# YBDuino.net
KiCad netlist of a schematic drawn in EAGLE
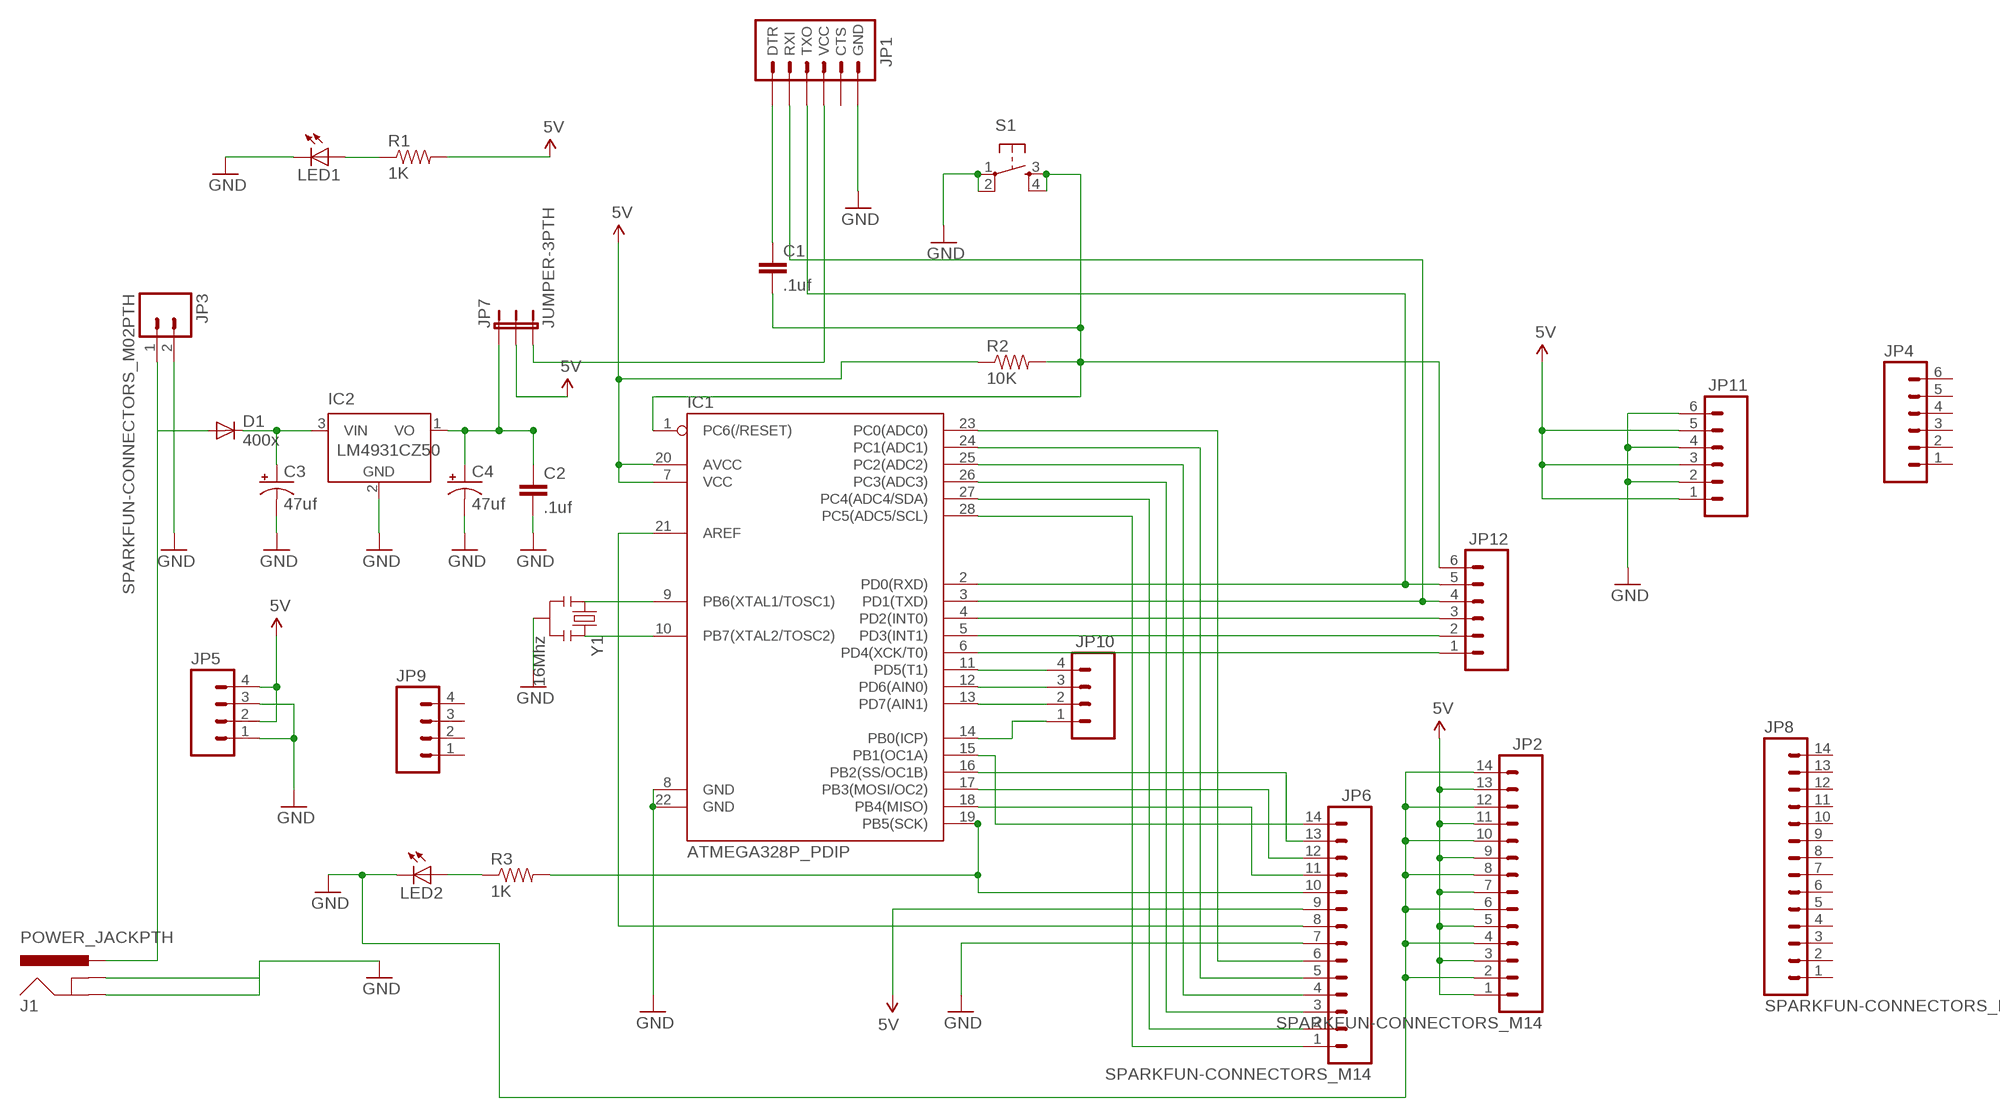
[diagram p0: schematic, sheet 1]

(export (version "E")
  (design (tool "Eeschema 10.0.6"))
  (components
    (comp (ref "C1")
      (value ".1uf")
      (footprint "eagle-import:CAP-PTH-SMALL")
      (libsource (lib "eagle-import") (part "CAPPTH"))
    )
    (comp (ref "C2")
      (value ".1uf")
      (footprint "eagle-import:CAP-PTH-SMALL")
      (libsource (lib "eagle-import") (part "CAPPTH"))
    )
    (comp (ref "C3")
      (value "47uf")
      (footprint "eagle-import:CPOL-RADIAL-100UF-25V")
      (libsource (lib "eagle-import") (part "CAP_POLPTH1"))
    )
    (comp (ref "C4")
      (value "47uf")
      (footprint "eagle-import:CPOL-RADIAL-100UF-25V")
      (libsource (lib "eagle-import") (part "CAP_POLPTH1"))
    )
    (comp (ref "D1")
      (value "400x")
      (footprint "eagle-import:C1702-05")
      (libsource (lib "eagle-import") (part "DIODE-C1702-05"))
    )
    (comp (ref "IC1")
      (value "ATMEGA328P_PDIP")
      (footprint "eagle-import:DIL28-3")
      (libsource (lib "eagle-import") (part "ATMEGA328P_PDIP"))
    )
    (comp (ref "IC2")
      (value "LM4931CZ50")
      (footprint "eagle-import:TO92")
      (fields (field (name "MF") "NATIONAL SEMICONDUCTOR") (field (name "MPN") "LM2936Z-3.0/NOPB"))
      (libsource (lib "eagle-import") (part "LM2936?Z-3.0"))
    )
    (comp (ref "J1")
      (value "POWER_JACKPTH")
      (footprint "eagle-import:POWER_JACK_PTH")
      (libsource (lib "eagle-import") (part "POWER_JACKPTH"))
    )
    (comp (ref "JP1")
      (value "SPARKFUN-CONNECTORS_ARDUINO_SERIAL_PROGRAMPTH-KIT")
      (footprint "eagle-import:SPARKFUN-CONNECTORS_1X06-KIT")
      (libsource (lib "eagle-import") (part "SPARKFUN-CONNECTORS_ARDUINO_SERIAL_PROGRAMPTH-KIT"))
    )
    (comp (ref "JP2")
      (value "SPARKFUN-CONNECTORS_M14")
      (footprint "eagle-import:SPARKFUN-CONNECTORS_1X14")
      (libsource (lib "eagle-import") (part "SPARKFUN-CONNECTORS_M14"))
    )
    (comp (ref "JP3")
      (value "SPARKFUN-CONNECTORS_M02PTH")
      (footprint "eagle-import:SPARKFUN-CONNECTORS_1X02")
      (libsource (lib "eagle-import") (part "SPARKFUN-CONNECTORS_M02PTH"))
    )
    (comp (ref "JP4")
      (value "SPARKFUN-CONNECTORS_M06SIP")
      (footprint "eagle-import:SPARKFUN-CONNECTORS_1X06")
      (libsource (lib "eagle-import") (part "SPARKFUN-CONNECTORS_M06SIP"))
    )
    (comp (ref "JP5")
      (value "SPARKFUN-CONNECTORS_M041X04_NO_SILK")
      (footprint "eagle-import:SPARKFUN-CONNECTORS_1X04_NO_SILK")
      (libsource (lib "eagle-import") (part "SPARKFUN-CONNECTORS_M041X04_NO_SILK"))
    )
    (comp (ref "JP6")
      (value "SPARKFUN-CONNECTORS_M14")
      (footprint "eagle-import:SPARKFUN-CONNECTORS_1X14")
      (libsource (lib "eagle-import") (part "SPARKFUN-CONNECTORS_M14"))
    )
    (comp (ref "JP7")
      (value "JUMPER-3PTH")
      (footprint "eagle-import:1X03")
      (libsource (lib "eagle-import") (part "JUMPER-3PTH"))
    )
    (comp (ref "JP8")
      (value "SPARKFUN-CONNECTORS_M14")
      (footprint "eagle-import:SPARKFUN-CONNECTORS_1X14")
      (libsource (lib "eagle-import") (part "SPARKFUN-CONNECTORS_M14"))
    )
    (comp (ref "JP9")
      (value "SPARKFUN-CONNECTORS_M041X04_NO_SILK")
      (footprint "eagle-import:SPARKFUN-CONNECTORS_1X04_NO_SILK")
      (libsource (lib "eagle-import") (part "SPARKFUN-CONNECTORS_M041X04_NO_SILK"))
    )
    (comp (ref "JP10")
      (value "SPARKFUN-CONNECTORS_M041X04_NO_SILK")
      (footprint "eagle-import:SPARKFUN-CONNECTORS_1X04_NO_SILK")
      (libsource (lib "eagle-import") (part "SPARKFUN-CONNECTORS_M041X04_NO_SILK"))
    )
    (comp (ref "JP11")
      (value "SPARKFUN-CONNECTORS_M06SIP")
      (footprint "eagle-import:SPARKFUN-CONNECTORS_1X06")
      (libsource (lib "eagle-import") (part "SPARKFUN-CONNECTORS_M06SIP"))
    )
    (comp (ref "JP12")
      (value "SPARKFUN-CONNECTORS_M06SIP")
      (footprint "eagle-import:SPARKFUN-CONNECTORS_1X06")
      (libsource (lib "eagle-import") (part "SPARKFUN-CONNECTORS_M06SIP"))
    )
    (comp (ref "LED1")
      (value "LED3MM")
      (footprint "eagle-import:LED3MM")
      (libsource (lib "eagle-import") (part "LED3MM"))
    )
    (comp (ref "LED2")
      (value "LED3MM")
      (footprint "eagle-import:LED3MM")
      (libsource (lib "eagle-import") (part "LED3MM"))
    )
    (comp (ref "R1")
      (value "1K")
      (footprint "eagle-import:AXIAL-0.1")
      (libsource (lib "eagle-import") (part "RESISTORPTH-1/4W-VERT"))
    )
    (comp (ref "R2")
      (value "10K")
      (footprint "eagle-import:AXIAL-0.1")
      (libsource (lib "eagle-import") (part "RESISTORPTH-1/4W-VERT"))
    )
    (comp (ref "R3")
      (value "1K")
      (footprint "eagle-import:AXIAL-0.1")
      (libsource (lib "eagle-import") (part "RESISTORPTH-1/4W-VERT"))
    )
    (comp (ref "S1")
      (value "TAC_SWITCHPTH")
      (footprint "eagle-import:TACTILE-PTH")
      (libsource (lib "eagle-import") (part "TAC_SWITCHPTH"))
    )
    (comp (ref "Y1")
      (value "16Mhz")
      (footprint "eagle-import:RESONATOR-PTH")
      (libsource (lib "eagle-import") (part "RESONATORPTH"))
    )
  )
  (nets
    (net (code "1") (name "5V") (class "Default")
      (node (ref "IC1") (pin "20") (pinfunction "AVCC_20") (pintype "bidirectional"))
      (node (ref "IC1") (pin "7") (pinfunction "VCC_7") (pintype "bidirectional"))
      (node (ref "JP11") (pin "1") (pinfunction "1_1") (pintype "passive"))
      (node (ref "JP11") (pin "3") (pinfunction "3_3") (pintype "passive"))
      (node (ref "JP11") (pin "5") (pinfunction "5_5") (pintype "passive"))
      (node (ref "JP2") (pin "1") (pinfunction "1_1") (pintype "passive"))
      (node (ref "JP2") (pin "11") (pinfunction "11_11") (pintype "passive"))
      (node (ref "JP2") (pin "13") (pinfunction "13_13") (pintype "passive"))
      (node (ref "JP2") (pin "3") (pinfunction "3_3") (pintype "passive"))
      (node (ref "JP2") (pin "5") (pinfunction "5_5") (pintype "passive"))
      (node (ref "JP2") (pin "7") (pinfunction "7_7") (pintype "passive"))
      (node (ref "JP2") (pin "9") (pinfunction "9_9") (pintype "passive"))
      (node (ref "JP5") (pin "2") (pinfunction "2_2") (pintype "passive"))
      (node (ref "JP5") (pin "4") (pinfunction "4_4") (pintype "passive"))
      (node (ref "JP6") (pin "9") (pinfunction "9_9") (pintype "passive"))
      (node (ref "JP7") (pin "2") (pinfunction "2_2") (pintype "passive"))
      (node (ref "R1") (pin "P$2") (pinfunction "2_P$2") (pintype "passive"))
      (node (ref "R2") (pin "P$1") (pinfunction "1_P$1") (pintype "passive"))
    )
    (net (code "2") (name "GND") (class "Default")
      (node (ref "C2") (pin "2") (pinfunction "2_2") (pintype "passive"))
      (node (ref "C3") (pin "2") (pinfunction "-_2") (pintype "passive"))
      (node (ref "C4") (pin "2") (pinfunction "-_2") (pintype "passive"))
      (node (ref "IC1") (pin "22") (pinfunction "GND_22") (pintype "bidirectional"))
      (node (ref "IC1") (pin "8") (pinfunction "GND_8") (pintype "bidirectional"))
      (node (ref "IC2") (pin "2") (pinfunction "GND_2") (pintype "passive"))
      (node (ref "J1") (pin "GND") (pinfunction "GND_GND") (pintype "bidirectional"))
      (node (ref "J1") (pin "GNDBREAK") (pinfunction "GNDBREAK_GNDBREAK") (pintype "bidirectional"))
      (node (ref "JP1") (pin "6") (pinfunction "GND_6") (pintype "passive"))
      (node (ref "JP11") (pin "2") (pinfunction "2_2") (pintype "passive"))
      (node (ref "JP11") (pin "4") (pinfunction "4_4") (pintype "passive"))
      (node (ref "JP11") (pin "6") (pinfunction "6_6") (pintype "passive"))
      (node (ref "JP2") (pin "10") (pinfunction "10_10") (pintype "passive"))
      (node (ref "JP2") (pin "12") (pinfunction "12_12") (pintype "passive"))
      (node (ref "JP2") (pin "14") (pinfunction "14_14") (pintype "passive"))
      (node (ref "JP2") (pin "2") (pinfunction "2_2") (pintype "passive"))
      (node (ref "JP2") (pin "4") (pinfunction "4_4") (pintype "passive"))
      (node (ref "JP2") (pin "6") (pinfunction "6_6") (pintype "passive"))
      (node (ref "JP2") (pin "8") (pinfunction "8_8") (pintype "passive"))
      (node (ref "JP3") (pin "2") (pinfunction "2_2") (pintype "passive"))
      (node (ref "JP5") (pin "1") (pinfunction "1_1") (pintype "passive"))
      (node (ref "JP5") (pin "3") (pinfunction "3_3") (pintype "passive"))
      (node (ref "JP6") (pin "7") (pinfunction "7_7") (pintype "passive"))
      (node (ref "LED1") (pin "K") (pinfunction "C_K") (pintype "passive"))
      (node (ref "LED2") (pin "K") (pinfunction "C_K") (pintype "passive"))
      (node (ref "S1") (pin "1") (pinfunction "1_1") (pintype "passive"))
      (node (ref "S1") (pin "2") (pinfunction "2_2") (pintype "passive"))
      (node (ref "Y1") (pin "2") (pinfunction "2_2") (pintype "passive"))
    )
    (net (code "3") (name "Net-(C3-+)") (class "Default")
      (node (ref "C3") (pin "1") (pinfunction "+_1") (pintype "passive"))
      (node (ref "D1") (pin "C") (pinfunction "C_C") (pintype "passive"))
      (node (ref "IC2") (pin "3") (pinfunction "VIN_3") (pintype "input"))
    )
    (net (code "4") (name "Net-(C4-+)") (class "Default")
      (node (ref "C2") (pin "1") (pinfunction "1_1") (pintype "passive"))
      (node (ref "C4") (pin "1") (pinfunction "+_1") (pintype "passive"))
      (node (ref "IC2") (pin "1") (pinfunction "VO_1") (pintype "passive"))
      (node (ref "JP7") (pin "1") (pinfunction "1_1") (pintype "passive"))
    )
    (net (code "5") (name "Net-(D1-PadA)") (class "Default")
      (node (ref "D1") (pin "A") (pinfunction "A_A") (pintype "passive"))
      (node (ref "J1") (pin "PWR") (pinfunction "PWR_PWR") (pintype "bidirectional"))
      (node (ref "JP3") (pin "1") (pinfunction "1_1") (pintype "passive"))
    )
    (net (code "6") (name "Net-(IC1-AREF)") (class "Default")
      (node (ref "IC1") (pin "21") (pinfunction "AREF_21") (pintype "bidirectional"))
      (node (ref "JP6") (pin "8") (pinfunction "8_8") (pintype "passive"))
    )
    (net (code "7") (name "Net-(IC1-PB0(ICP))") (class "Default")
      (node (ref "IC1") (pin "14") (pinfunction "PB0(ICP)_14") (pintype "bidirectional"))
      (node (ref "JP10") (pin "1") (pinfunction "1_1") (pintype "passive"))
    )
    (net (code "8") (name "Net-(IC1-PB1(OC1A))") (class "Default")
      (node (ref "IC1") (pin "15") (pinfunction "PB1(OC1A)_15") (pintype "bidirectional"))
      (node (ref "JP6") (pin "14") (pinfunction "14_14") (pintype "passive"))
    )
    (net (code "9") (name "Net-(IC1-PB2(SS{slash}OC1B))") (class "Default")
      (node (ref "IC1") (pin "16") (pinfunction "PB2(SS/OC1B)_16") (pintype "bidirectional"))
      (node (ref "JP6") (pin "13") (pinfunction "13_13") (pintype "passive"))
    )
    (net (code "10") (name "Net-(IC1-PB3(MOSI{slash}OC2))") (class "Default")
      (node (ref "IC1") (pin "17") (pinfunction "PB3(MOSI/OC2)_17") (pintype "bidirectional"))
      (node (ref "JP6") (pin "12") (pinfunction "12_12") (pintype "passive"))
    )
    (net (code "11") (name "Net-(IC1-PB4(MISO))") (class "Default")
      (node (ref "IC1") (pin "18") (pinfunction "PB4(MISO)_18") (pintype "bidirectional"))
      (node (ref "JP6") (pin "11") (pinfunction "11_11") (pintype "passive"))
    )
    (net (code "12") (name "Net-(IC1-PB5(SCK))") (class "Default")
      (node (ref "IC1") (pin "19") (pinfunction "PB5(SCK)_19") (pintype "bidirectional"))
      (node (ref "JP6") (pin "10") (pinfunction "10_10") (pintype "passive"))
      (node (ref "R3") (pin "P$2") (pinfunction "2_P$2") (pintype "passive"))
    )
    (net (code "13") (name "Net-(IC1-PB6(XTAL1{slash}TOSC1))") (class "Default")
      (node (ref "IC1") (pin "9") (pinfunction "PB6(XTAL1/TOSC1)_9") (pintype "bidirectional"))
      (node (ref "Y1") (pin "1") (pinfunction "1_1") (pintype "passive"))
    )
    (net (code "14") (name "Net-(IC1-PB7(XTAL2{slash}TOSC2))") (class "Default")
      (node (ref "IC1") (pin "10") (pinfunction "PB7(XTAL2/TOSC2)_10") (pintype "bidirectional"))
      (node (ref "Y1") (pin "3") (pinfunction "3_3") (pintype "passive"))
    )
    (net (code "15") (name "Net-(IC1-PC0(ADC0))") (class "Default")
      (node (ref "IC1") (pin "23") (pinfunction "PC0(ADC0)_23") (pintype "bidirectional"))
      (node (ref "JP6") (pin "6") (pinfunction "6_6") (pintype "passive"))
    )
    (net (code "16") (name "Net-(IC1-PC1(ADC1))") (class "Default")
      (node (ref "IC1") (pin "24") (pinfunction "PC1(ADC1)_24") (pintype "bidirectional"))
      (node (ref "JP6") (pin "5") (pinfunction "5_5") (pintype "passive"))
    )
    (net (code "17") (name "Net-(IC1-PC2(ADC2))") (class "Default")
      (node (ref "IC1") (pin "25") (pinfunction "PC2(ADC2)_25") (pintype "bidirectional"))
      (node (ref "JP6") (pin "4") (pinfunction "4_4") (pintype "passive"))
    )
    (net (code "18") (name "Net-(IC1-PC3(ADC3))") (class "Default")
      (node (ref "IC1") (pin "26") (pinfunction "PC3(ADC3)_26") (pintype "bidirectional"))
      (node (ref "JP6") (pin "3") (pinfunction "3_3") (pintype "passive"))
    )
    (net (code "19") (name "Net-(IC1-PC4(ADC4{slash}SDA))") (class "Default")
      (node (ref "IC1") (pin "27") (pinfunction "PC4(ADC4/SDA)_27") (pintype "bidirectional"))
      (node (ref "JP6") (pin "2") (pinfunction "2_2") (pintype "passive"))
    )
    (net (code "20") (name "Net-(IC1-PC5(ADC5{slash}SCL))") (class "Default")
      (node (ref "IC1") (pin "28") (pinfunction "PC5(ADC5/SCL)_28") (pintype "bidirectional"))
      (node (ref "JP6") (pin "1") (pinfunction "1_1") (pintype "passive"))
    )
    (net (code "21") (name "Net-(IC1-PC6({slash}RESET))") (class "Default")
      (node (ref "C1") (pin "2") (pinfunction "2_2") (pintype "passive"))
      (node (ref "IC1") (pin "1") (pinfunction "PC6(/RESET)_1") (pintype "bidirectional"))
      (node (ref "JP12") (pin "6") (pinfunction "6_6") (pintype "passive"))
      (node (ref "R2") (pin "P$2") (pinfunction "2_P$2") (pintype "passive"))
      (node (ref "S1") (pin "3") (pinfunction "3_3") (pintype "passive"))
      (node (ref "S1") (pin "4") (pinfunction "4_4") (pintype "passive"))
    )
    (net (code "22") (name "Net-(IC1-PD0(RXD))") (class "Default")
      (node (ref "IC1") (pin "2") (pinfunction "PD0(RXD)_2") (pintype "bidirectional"))
      (node (ref "JP1") (pin "3") (pinfunction "TXO_3") (pintype "passive"))
      (node (ref "JP12") (pin "5") (pinfunction "5_5") (pintype "passive"))
    )
    (net (code "23") (name "Net-(IC1-PD1(TXD))") (class "Default")
      (node (ref "IC1") (pin "3") (pinfunction "PD1(TXD)_3") (pintype "bidirectional"))
      (node (ref "JP1") (pin "2") (pinfunction "RXI_2") (pintype "passive"))
      (node (ref "JP12") (pin "4") (pinfunction "4_4") (pintype "passive"))
    )
    (net (code "24") (name "Net-(IC1-PD2(INT0))") (class "Default")
      (node (ref "IC1") (pin "4") (pinfunction "PD2(INT0)_4") (pintype "bidirectional"))
      (node (ref "JP12") (pin "3") (pinfunction "3_3") (pintype "passive"))
    )
    (net (code "25") (name "Net-(IC1-PD3(INT1))") (class "Default")
      (node (ref "IC1") (pin "5") (pinfunction "PD3(INT1)_5") (pintype "bidirectional"))
      (node (ref "JP12") (pin "2") (pinfunction "2_2") (pintype "passive"))
    )
    (net (code "26") (name "Net-(IC1-PD4(XCK{slash}T0))") (class "Default")
      (node (ref "IC1") (pin "6") (pinfunction "PD4(XCK/T0)_6") (pintype "bidirectional"))
      (node (ref "JP12") (pin "1") (pinfunction "1_1") (pintype "passive"))
    )
    (net (code "27") (name "Net-(IC1-PD5(T1))") (class "Default")
      (node (ref "IC1") (pin "11") (pinfunction "PD5(T1)_11") (pintype "bidirectional"))
      (node (ref "JP10") (pin "4") (pinfunction "4_4") (pintype "passive"))
    )
    (net (code "28") (name "Net-(IC1-PD6(AIN0))") (class "Default")
      (node (ref "IC1") (pin "12") (pinfunction "PD6(AIN0)_12") (pintype "bidirectional"))
      (node (ref "JP10") (pin "3") (pinfunction "3_3") (pintype "passive"))
    )
    (net (code "29") (name "Net-(IC1-PD7(AIN1))") (class "Default")
      (node (ref "IC1") (pin "13") (pinfunction "PD7(AIN1)_13") (pintype "bidirectional"))
      (node (ref "JP10") (pin "2") (pinfunction "2_2") (pintype "passive"))
    )
    (net (code "30") (name "Net-(JP1-DTR)") (class "Default")
      (node (ref "C1") (pin "1") (pinfunction "1_1") (pintype "passive"))
      (node (ref "JP1") (pin "1") (pinfunction "DTR_1") (pintype "passive"))
    )
    (net (code "31") (name "Net-(JP1-VCC)") (class "Default")
      (node (ref "JP1") (pin "4") (pinfunction "VCC_4") (pintype "passive"))
      (node (ref "JP7") (pin "3") (pinfunction "3_3") (pintype "passive"))
    )
    (net (code "32") (name "Net-(R1-1)") (class "Default")
      (node (ref "LED1") (pin "A") (pinfunction "A_A") (pintype "passive"))
      (node (ref "R1") (pin "P$1") (pinfunction "1_P$1") (pintype "passive"))
    )
    (net (code "33") (name "Net-(R3-1)") (class "Default")
      (node (ref "LED2") (pin "A") (pinfunction "A_A") (pintype "passive"))
      (node (ref "R3") (pin "P$1") (pinfunction "1_P$1") (pintype "passive"))
    )
    (net (code "34") (name "unconnected-(JP1-CTS-Pad5)") (class "Default")
      (node (ref "JP1") (pin "5") (pinfunction "CTS_5") (pintype "passive"))
    )
    (net (code "35") (name "unconnected-(JP4-Pad1)") (class "Default")
      (node (ref "JP4") (pin "1") (pinfunction "1_1") (pintype "passive"))
    )
    (net (code "36") (name "unconnected-(JP4-Pad2)") (class "Default")
      (node (ref "JP4") (pin "2") (pinfunction "2_2") (pintype "passive"))
    )
    (net (code "37") (name "unconnected-(JP4-Pad3)") (class "Default")
      (node (ref "JP4") (pin "3") (pinfunction "3_3") (pintype "passive"))
    )
    (net (code "38") (name "unconnected-(JP4-Pad4)") (class "Default")
      (node (ref "JP4") (pin "4") (pinfunction "4_4") (pintype "passive"))
    )
    (net (code "39") (name "unconnected-(JP4-Pad5)") (class "Default")
      (node (ref "JP4") (pin "5") (pinfunction "5_5") (pintype "passive"))
    )
    (net (code "40") (name "unconnected-(JP4-Pad6)") (class "Default")
      (node (ref "JP4") (pin "6") (pinfunction "6_6") (pintype "passive"))
    )
    (net (code "41") (name "unconnected-(JP8-Pad1)") (class "Default")
      (node (ref "JP8") (pin "1") (pinfunction "1_1") (pintype "passive"))
    )
    (net (code "42") (name "unconnected-(JP8-Pad2)") (class "Default")
      (node (ref "JP8") (pin "2") (pinfunction "2_2") (pintype "passive"))
    )
    (net (code "43") (name "unconnected-(JP8-Pad3)") (class "Default")
      (node (ref "JP8") (pin "3") (pinfunction "3_3") (pintype "passive"))
    )
    (net (code "44") (name "unconnected-(JP8-Pad4)") (class "Default")
      (node (ref "JP8") (pin "4") (pinfunction "4_4") (pintype "passive"))
    )
    (net (code "45") (name "unconnected-(JP8-Pad5)") (class "Default")
      (node (ref "JP8") (pin "5") (pinfunction "5_5") (pintype "passive"))
    )
    (net (code "46") (name "unconnected-(JP8-Pad6)") (class "Default")
      (node (ref "JP8") (pin "6") (pinfunction "6_6") (pintype "passive"))
    )
    (net (code "47") (name "unconnected-(JP8-Pad7)") (class "Default")
      (node (ref "JP8") (pin "7") (pinfunction "7_7") (pintype "passive"))
    )
    (net (code "48") (name "unconnected-(JP8-Pad8)") (class "Default")
      (node (ref "JP8") (pin "8") (pinfunction "8_8") (pintype "passive"))
    )
    (net (code "49") (name "unconnected-(JP8-Pad9)") (class "Default")
      (node (ref "JP8") (pin "9") (pinfunction "9_9") (pintype "passive"))
    )
    (net (code "50") (name "unconnected-(JP8-Pad10)") (class "Default")
      (node (ref "JP8") (pin "10") (pinfunction "10_10") (pintype "passive"))
    )
    (net (code "51") (name "unconnected-(JP8-Pad11)") (class "Default")
      (node (ref "JP8") (pin "11") (pinfunction "11_11") (pintype "passive"))
    )
    (net (code "52") (name "unconnected-(JP8-Pad12)") (class "Default")
      (node (ref "JP8") (pin "12") (pinfunction "12_12") (pintype "passive"))
    )
    (net (code "53") (name "unconnected-(JP8-Pad13)") (class "Default")
      (node (ref "JP8") (pin "13") (pinfunction "13_13") (pintype "passive"))
    )
    (net (code "54") (name "unconnected-(JP8-Pad14)") (class "Default")
      (node (ref "JP8") (pin "14") (pinfunction "14_14") (pintype "passive"))
    )
    (net (code "55") (name "unconnected-(JP9-Pad1)") (class "Default")
      (node (ref "JP9") (pin "1") (pinfunction "1_1") (pintype "passive"))
    )
    (net (code "56") (name "unconnected-(JP9-Pad2)") (class "Default")
      (node (ref "JP9") (pin "2") (pinfunction "2_2") (pintype "passive"))
    )
    (net (code "57") (name "unconnected-(JP9-Pad3)") (class "Default")
      (node (ref "JP9") (pin "3") (pinfunction "3_3") (pintype "passive"))
    )
    (net (code "58") (name "unconnected-(JP9-Pad4)") (class "Default")
      (node (ref "JP9") (pin "4") (pinfunction "4_4") (pintype "passive"))
    )
  )
)
